# ui_IO.net
KiCad netlist of a schematic drawn in Altium Designer
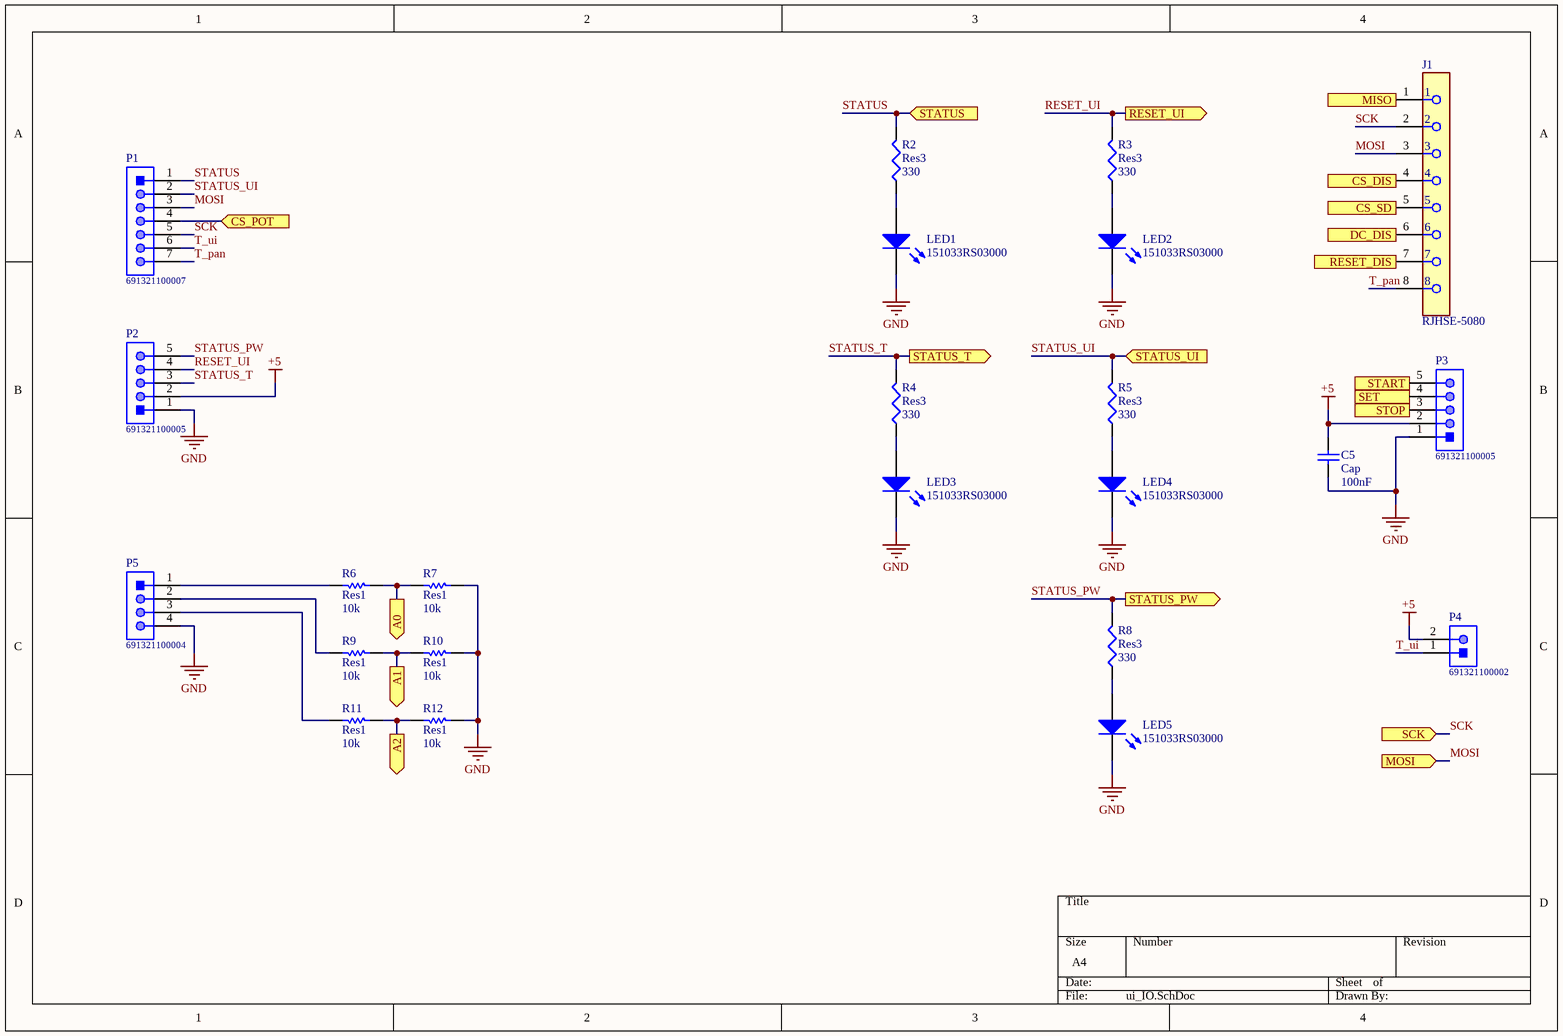
[diagram p0: ui_IO.SchDoc]

(export (version "E")
  (design (tool "Eeschema 10.0.6"))
  (components
    (comp (ref "C5")
      (value "Cap")
      (footprint "RAD-0.3")
      (description "Capacitor")
      (fields (field (name "ALTIUM_VALUE") "100nF") (field (name "PUBLISHER") "Altium Limited"))
      (libsource (lib "Miscellaneous Devices") (part "Cap"))
    )
    (comp (ref "J1")
      (value "RJHSE-5080")
      (footprint "FP-RJHSE-5080-MFG")
      (description "CONN MOD JACK 8P8C R/A UNSHLD")
      (fields
        (field (name "OCTOPART") "https://octopart.com/rjhse-5080-amphenol-45060")
        (field (name "MANUFACTURER") "Amphenol")
      )
      (libsource (lib "Altium Content Vault") (part "b0a0b555dd3abf3683e7c330df25cc4"))
    )
    (comp (ref "LED1")
      (value "151033RS03000")
      (footprint "Type 3mm")
      (description "THT LED round mono-color waterclear, WL-TMRW, Red")
      (fields (field (name "MANUFACTURER") "Wuerth Elektronik"))
      (libsource (lib "Altium Content Vault") (part "WE-LED_K1A2-2"))
    )
    (comp (ref "LED2")
      (value "151033RS03000")
      (footprint "Type 3mm")
      (description "THT LED round mono-color waterclear, WL-TMRW, Red")
      (fields (field (name "MANUFACTURER") "Wuerth Elektronik"))
      (libsource (lib "Altium Content Vault") (part "WE-LED_K1A2-2"))
    )
    (comp (ref "LED3")
      (value "151033RS03000")
      (footprint "Type 3mm")
      (description "THT LED round mono-color waterclear, WL-TMRW, Red")
      (fields (field (name "MANUFACTURER") "Wuerth Elektronik"))
      (libsource (lib "Altium Content Vault") (part "WE-LED_K1A2-2"))
    )
    (comp (ref "LED4")
      (value "151033RS03000")
      (footprint "Type 3mm")
      (description "THT LED round mono-color waterclear, WL-TMRW, Red")
      (fields (field (name "MANUFACTURER") "Wuerth Elektronik"))
      (libsource (lib "Altium Content Vault") (part "WE-LED_K1A2-2"))
    )
    (comp (ref "LED5")
      (value "151033RS03000")
      (footprint "Type 3mm")
      (description "THT LED round mono-color waterclear, WL-TMRW, Red")
      (fields (field (name "MANUFACTURER") "Wuerth Elektronik"))
      (libsource (lib "Altium Content Vault") (part "WE-LED_K1A2-2"))
    )
    (comp (ref "P1")
      (value "691321100007")
      (footprint "691321100007")
      (description "Serie 3211 - 3.50mm Vertical PCB Header WR-TBL, 7 pin")
      (fields (field (name "MANUFACTURER") "Wurth Elektronik") (field (name "PUBLISHER") "WurthElektronik"))
      (libsource (lib "Altium Content Vault") (part "WE-CN-1P-M-R7"))
    )
    (comp (ref "P2")
      (value "691321100005")
      (footprint "691321100005")
      (description "Serie 3211 - 3.50mm Vertical PCB Header WR-TBL, 5 pin")
      (fields (field (name "MANUFACTURER") "Wurth Elektronik") (field (name "PUBLISHER") "WurthElektronik"))
      (libsource (lib "") (part "WE-CN-1P-M-R5_1"))
    )
    (comp (ref "P3")
      (value "691321100005")
      (footprint "691321100005")
      (description "Serie 3211 - 3.50mm Vertical PCB Header WR-TBL, 5 pin")
      (fields (field (name "MANUFACTURER") "Wurth Elektronik") (field (name "PUBLISHER") "WurthElektronik"))
      (libsource (lib "Altium Content Vault") (part "WE-CN-1P-M-R5"))
    )
    (comp (ref "P4")
      (value "691321100002")
      (footprint "691321100002")
      (description "Serie 3211 - 3.50mm Vertical PCB Header WR-TBL, 2 pin")
      (fields (field (name "MANUFACTURER") "Wurth Elektronik") (field (name "PUBLISHER") "WurthElektronik"))
      (libsource (lib "Altium Content Vault") (part "WE-CN-1P-M-R2"))
    )
    (comp (ref "P5")
      (value "691321100004")
      (footprint "691321100004")
      (description "Serie 3211 - 3.50mm Vertical PCB Header WR-TBL, 4 pin")
      (fields (field (name "MANUFACTURER") "Wurth Elektronik") (field (name "PUBLISHER") "WurthElektronik"))
      (libsource (lib "Altium Content Vault") (part "WE-CN-1P-M-R4"))
    )
    (comp (ref "R2")
      (value "Res3")
      (footprint "AXIAL-0.4")
      (description "Resistor")
      (fields (field (name "ALTIUM_VALUE") "330") (field (name "PUBLISHER") "Altium Limited"))
      (libsource (lib "Miscellaneous Devices") (part "Res3"))
    )
    (comp (ref "R3")
      (value "Res3")
      (footprint "AXIAL-0.4")
      (description "Resistor")
      (fields (field (name "ALTIUM_VALUE") "330") (field (name "PUBLISHER") "Altium Limited"))
      (libsource (lib "Miscellaneous Devices") (part "Res3"))
    )
    (comp (ref "R4")
      (value "Res3")
      (footprint "AXIAL-0.4")
      (description "Resistor")
      (fields (field (name "ALTIUM_VALUE") "330") (field (name "PUBLISHER") "Altium Limited"))
      (libsource (lib "Miscellaneous Devices") (part "Res3"))
    )
    (comp (ref "R5")
      (value "Res3")
      (footprint "AXIAL-0.4")
      (description "Resistor")
      (fields (field (name "ALTIUM_VALUE") "330") (field (name "PUBLISHER") "Altium Limited"))
      (libsource (lib "Miscellaneous Devices") (part "Res3"))
    )
    (comp (ref "R6")
      (value "Res1")
      (footprint "AXIAL-0.4")
      (description "Resistor")
      (fields (field (name "ALTIUM_VALUE") "10k") (field (name "PUBLISHER") "Altium Limited"))
      (libsource (lib "Miscellaneous Devices") (part "Res1"))
    )
    (comp (ref "R7")
      (value "Res1")
      (footprint "AXIAL-0.4")
      (description "Resistor")
      (fields (field (name "ALTIUM_VALUE") "10k") (field (name "PUBLISHER") "Altium Limited"))
      (libsource (lib "Miscellaneous Devices") (part "Res1"))
    )
    (comp (ref "R8")
      (value "Res3")
      (footprint "AXIAL-0.4")
      (description "Resistor")
      (fields (field (name "ALTIUM_VALUE") "330") (field (name "PUBLISHER") "Altium Limited"))
      (libsource (lib "Miscellaneous Devices") (part "Res3"))
    )
    (comp (ref "R9")
      (value "Res1")
      (footprint "AXIAL-0.4")
      (description "Resistor")
      (fields (field (name "ALTIUM_VALUE") "10k") (field (name "PUBLISHER") "Altium Limited"))
      (libsource (lib "Miscellaneous Devices") (part "Res1"))
    )
    (comp (ref "R10")
      (value "Res1")
      (footprint "AXIAL-0.4")
      (description "Resistor")
      (fields (field (name "ALTIUM_VALUE") "10k") (field (name "PUBLISHER") "Altium Limited"))
      (libsource (lib "Miscellaneous Devices") (part "Res1"))
    )
    (comp (ref "R11")
      (value "Res1")
      (footprint "AXIAL-0.4")
      (description "Resistor")
      (fields (field (name "ALTIUM_VALUE") "10k") (field (name "PUBLISHER") "Altium Limited"))
      (libsource (lib "Miscellaneous Devices") (part "Res1"))
    )
    (comp (ref "R12")
      (value "Res1")
      (footprint "AXIAL-0.4")
      (description "Resistor")
      (fields (field (name "ALTIUM_VALUE") "10k") (field (name "PUBLISHER") "Altium Limited"))
      (libsource (lib "Miscellaneous Devices") (part "Res1"))
    )
  )
  (nets
    (net (code "1") (name "+5") (class "Default")
      (node (ref "C5") (pin "2") (pinfunction "2_2") (pintype "passive"))
      (node (ref "P2") (pin "2") (pinfunction "2_2") (pintype "passive"))
      (node (ref "P3") (pin "2") (pinfunction "2_2") (pintype "passive"))
      (node (ref "P4") (pin "2") (pinfunction "2_2") (pintype "passive"))
    )
    (net (code "2") (name "/A0") (class "Default")
      (node (ref "R6") (pin "1") (pinfunction "1_1") (pintype "passive"))
      (node (ref "R7") (pin "2") (pinfunction "2_2") (pintype "passive"))
    )
    (net (code "3") (name "/A1") (class "Default")
      (node (ref "R10") (pin "2") (pinfunction "2_2") (pintype "passive"))
      (node (ref "R9") (pin "1") (pinfunction "1_1") (pintype "passive"))
    )
    (net (code "4") (name "/A2") (class "Default")
      (node (ref "R11") (pin "1") (pinfunction "1_1") (pintype "passive"))
      (node (ref "R12") (pin "2") (pinfunction "2_2") (pintype "passive"))
    )
    (net (code "5") (name "/CS_DIS") (class "Default")
      (node (ref "J1") (pin "4") (pinfunction "4_4") (pintype "passive"))
    )
    (net (code "6") (name "/CS_POT") (class "Default")
      (node (ref "P1") (pin "4") (pinfunction "4_4") (pintype "passive"))
    )
    (net (code "7") (name "/CS_SD") (class "Default")
      (node (ref "J1") (pin "5") (pinfunction "5_5") (pintype "passive"))
    )
    (net (code "8") (name "/DC_DIS") (class "Default")
      (node (ref "J1") (pin "6") (pinfunction "6_6") (pintype "passive"))
    )
    (net (code "9") (name "/MISO") (class "Default")
      (node (ref "J1") (pin "1") (pinfunction "1_1") (pintype "passive"))
    )
    (net (code "10") (name "/MOSI") (class "Default")
      (node (ref "J1") (pin "3") (pinfunction "3_3") (pintype "passive"))
      (node (ref "P1") (pin "3") (pinfunction "3_3") (pintype "passive"))
    )
    (net (code "11") (name "/RESET_DIS") (class "Default")
      (node (ref "J1") (pin "7") (pinfunction "7_7") (pintype "passive"))
    )
    (net (code "12") (name "/RESET_UI") (class "Default")
      (node (ref "P2") (pin "4") (pinfunction "4_4") (pintype "passive"))
      (node (ref "R3") (pin "2") (pinfunction "2_2") (pintype "passive"))
    )
    (net (code "13") (name "/SCK") (class "Default")
      (node (ref "J1") (pin "2") (pinfunction "2_2") (pintype "passive"))
      (node (ref "P1") (pin "5") (pinfunction "5_5") (pintype "passive"))
    )
    (net (code "14") (name "/SET") (class "Default")
      (node (ref "P3") (pin "4") (pinfunction "4_4") (pintype "passive"))
    )
    (net (code "15") (name "/START") (class "Default")
      (node (ref "P3") (pin "5") (pinfunction "5_5") (pintype "passive"))
    )
    (net (code "16") (name "/STATUS") (class "Default")
      (node (ref "P1") (pin "1") (pinfunction "1_1") (pintype "passive"))
      (node (ref "R2") (pin "2") (pinfunction "2_2") (pintype "passive"))
    )
    (net (code "17") (name "/STATUS_PW") (class "Default")
      (node (ref "P2") (pin "5") (pinfunction "5_5") (pintype "passive"))
      (node (ref "R8") (pin "2") (pinfunction "2_2") (pintype "passive"))
    )
    (net (code "18") (name "/STATUS_T") (class "Default")
      (node (ref "P2") (pin "3") (pinfunction "3_3") (pintype "passive"))
      (node (ref "R4") (pin "2") (pinfunction "2_2") (pintype "passive"))
    )
    (net (code "19") (name "/STATUS_UI") (class "Default")
      (node (ref "P1") (pin "2") (pinfunction "2_2") (pintype "passive"))
      (node (ref "R5") (pin "2") (pinfunction "2_2") (pintype "passive"))
    )
    (net (code "20") (name "/STOP") (class "Default")
      (node (ref "P3") (pin "3") (pinfunction "3_3") (pintype "passive"))
    )
    (net (code "21") (name "/T_pan") (class "Default")
      (node (ref "J1") (pin "8") (pinfunction "8_8") (pintype "passive"))
      (node (ref "P1") (pin "7") (pinfunction "7_7") (pintype "passive"))
    )
    (net (code "22") (name "/T_ui") (class "Default")
      (node (ref "P1") (pin "6") (pinfunction "6_6") (pintype "passive"))
      (node (ref "P4") (pin "1") (pinfunction "1_1") (pintype "passive"))
    )
    (net (code "23") (name "GND") (class "Default")
      (node (ref "C5") (pin "1") (pinfunction "1_1") (pintype "passive"))
      (node (ref "LED1") (pin "1") (pinfunction "K_1") (pintype "passive"))
      (node (ref "LED2") (pin "1") (pinfunction "K_1") (pintype "passive"))
      (node (ref "LED3") (pin "1") (pinfunction "K_1") (pintype "passive"))
      (node (ref "LED4") (pin "1") (pinfunction "K_1") (pintype "passive"))
      (node (ref "LED5") (pin "1") (pinfunction "K_1") (pintype "passive"))
      (node (ref "P2") (pin "1") (pinfunction "1_1") (pintype "passive"))
      (node (ref "P3") (pin "1") (pinfunction "1_1") (pintype "passive"))
      (node (ref "P5") (pin "4") (pinfunction "4_4") (pintype "passive"))
      (node (ref "R10") (pin "1") (pinfunction "1_1") (pintype "passive"))
      (node (ref "R12") (pin "1") (pinfunction "1_1") (pintype "passive"))
      (node (ref "R7") (pin "1") (pinfunction "1_1") (pintype "passive"))
    )
    (net (code "24") (name "Net-(LED1-A)") (class "Default")
      (node (ref "LED1") (pin "2") (pinfunction "A_2") (pintype "passive"))
      (node (ref "R2") (pin "1") (pinfunction "1_1") (pintype "passive"))
    )
    (net (code "25") (name "Net-(LED2-A)") (class "Default")
      (node (ref "LED2") (pin "2") (pinfunction "A_2") (pintype "passive"))
      (node (ref "R3") (pin "1") (pinfunction "1_1") (pintype "passive"))
    )
    (net (code "26") (name "Net-(LED3-A)") (class "Default")
      (node (ref "LED3") (pin "2") (pinfunction "A_2") (pintype "passive"))
      (node (ref "R4") (pin "1") (pinfunction "1_1") (pintype "passive"))
    )
    (net (code "27") (name "Net-(LED4-A)") (class "Default")
      (node (ref "LED4") (pin "2") (pinfunction "A_2") (pintype "passive"))
      (node (ref "R5") (pin "1") (pinfunction "1_1") (pintype "passive"))
    )
    (net (code "28") (name "Net-(LED5-A)") (class "Default")
      (node (ref "LED5") (pin "2") (pinfunction "A_2") (pintype "passive"))
      (node (ref "R8") (pin "1") (pinfunction "1_1") (pintype "passive"))
    )
    (net (code "29") (name "Net-(P5-Pad1)") (class "Default")
      (node (ref "P5") (pin "1") (pinfunction "1_1") (pintype "passive"))
      (node (ref "R6") (pin "2") (pinfunction "2_2") (pintype "passive"))
    )
    (net (code "30") (name "Net-(P5-Pad2)") (class "Default")
      (node (ref "P5") (pin "2") (pinfunction "2_2") (pintype "passive"))
      (node (ref "R9") (pin "2") (pinfunction "2_2") (pintype "passive"))
    )
    (net (code "31") (name "Net-(P5-Pad3)") (class "Default")
      (node (ref "P5") (pin "3") (pinfunction "3_3") (pintype "passive"))
      (node (ref "R11") (pin "2") (pinfunction "2_2") (pintype "passive"))
    )
  )
)
